# PiDGCv2.net
KiCad netlist of a schematic drawn in EAGLE
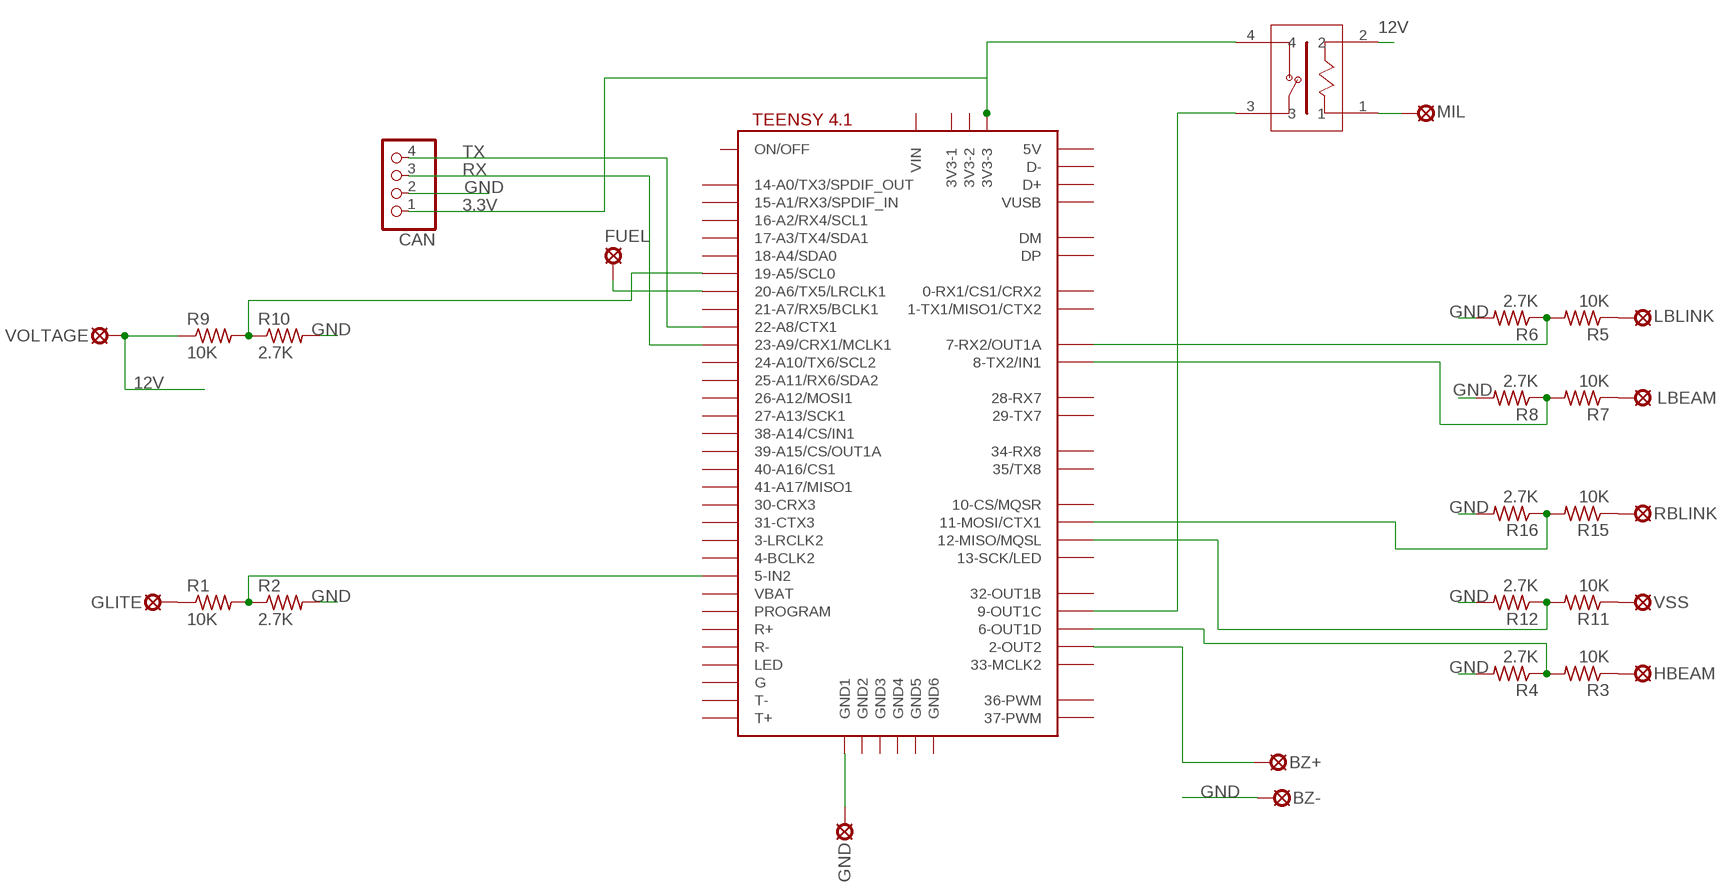
[diagram p0: schematic, sheet 1]

(export (version "E")
  (design (tool "Eeschema 10.0.6"))
  (components
    (comp (ref "BZ+")
      (value "LSP10")
      (footprint "eagle-import:LSP10")
      (libsource (lib "eagle-import") (part "LSP10"))
    )
    (comp (ref "BZ-")
      (value "LSP10")
      (footprint "eagle-import:LSP10")
      (libsource (lib "eagle-import") (part "LSP10"))
    )
    (comp (ref "CAN")
      (value "PINHD-1X4")
      (footprint "eagle-import:1X04")
      (libsource (lib "eagle-import") (part "PINHD-1X4"))
    )
    (comp (ref "FUEL")
      (value "LSP10")
      (footprint "eagle-import:LSP10")
      (libsource (lib "eagle-import") (part "LSP10"))
    )
    (comp (ref "GLITE")
      (value "LSP10")
      (footprint "eagle-import:LSP10")
      (libsource (lib "eagle-import") (part "LSP10"))
    )
    (comp (ref "GND")
      (value "LSP10")
      (footprint "eagle-import:LSP10")
      (libsource (lib "eagle-import") (part "LSP10"))
    )
    (comp (ref "HBEAM")
      (value "LSP10")
      (footprint "eagle-import:LSP10")
      (libsource (lib "eagle-import") (part "LSP10"))
    )
    (comp (ref "LBEAM")
      (value "LSP10")
      (footprint "eagle-import:LSP10")
      (libsource (lib "eagle-import") (part "LSP10"))
    )
    (comp (ref "LBLINK")
      (value "LSP10")
      (footprint "eagle-import:LSP10")
      (libsource (lib "eagle-import") (part "LSP10"))
    )
    (comp (ref "MIL")
      (value "LSP10")
      (footprint "eagle-import:LSP10")
      (libsource (lib "eagle-import") (part "LSP10"))
    )
    (comp (ref "MIL_RELAY")
      (value "BR-1050-VP")
      (footprint "eagle-import:RELAY")
      (libsource (lib "eagle-import") (part "BR-1050-VP"))
    )
    (comp (ref "R1")
      (value "10K")
      (footprint "eagle-import:0204_7")
      (libsource (lib "eagle-import") (part "R-US_0204/7"))
    )
    (comp (ref "R2")
      (value "2.7K")
      (footprint "eagle-import:0204_7")
      (libsource (lib "eagle-import") (part "R-US_0204/7"))
    )
    (comp (ref "R3")
      (value "10K")
      (footprint "eagle-import:0204_7")
      (libsource (lib "eagle-import") (part "R-US_0204/7"))
    )
    (comp (ref "R4")
      (value "2.7K")
      (footprint "eagle-import:0204_7")
      (libsource (lib "eagle-import") (part "R-US_0204/7"))
    )
    (comp (ref "R5")
      (value "10K")
      (footprint "eagle-import:0204_7")
      (libsource (lib "eagle-import") (part "R-US_0204/7"))
    )
    (comp (ref "R6")
      (value "2.7K")
      (footprint "eagle-import:0204_7")
      (libsource (lib "eagle-import") (part "R-US_0204/7"))
    )
    (comp (ref "R7")
      (value "10K")
      (footprint "eagle-import:0204_7")
      (libsource (lib "eagle-import") (part "R-US_0204/7"))
    )
    (comp (ref "R8")
      (value "2.7K")
      (footprint "eagle-import:0204_7")
      (libsource (lib "eagle-import") (part "R-US_0204/7"))
    )
    (comp (ref "R9")
      (value "10K")
      (footprint "eagle-import:0204_7")
      (libsource (lib "eagle-import") (part "R-US_0204/7"))
    )
    (comp (ref "R10")
      (value "2.7K")
      (footprint "eagle-import:0204_7")
      (libsource (lib "eagle-import") (part "R-US_0204/7"))
    )
    (comp (ref "R11")
      (value "10K")
      (footprint "eagle-import:0204_7")
      (libsource (lib "eagle-import") (part "R-US_0204/7"))
    )
    (comp (ref "R12")
      (value "2.7K")
      (footprint "eagle-import:0204_7")
      (libsource (lib "eagle-import") (part "R-US_0204/7"))
    )
    (comp (ref "R15")
      (value "10K")
      (footprint "eagle-import:0204_7")
      (libsource (lib "eagle-import") (part "R-US_0204/7"))
    )
    (comp (ref "R16")
      (value "2.7K")
      (footprint "eagle-import:0204_7")
      (libsource (lib "eagle-import") (part "R-US_0204/7"))
    )
    (comp (ref "RBLINK")
      (value "LSP10")
      (footprint "eagle-import:LSP10")
      (libsource (lib "eagle-import") (part "LSP10"))
    )
    (comp (ref "U$1")
      (value "TEENSY41")
      (footprint "eagle-import:TEENSY41")
      (libsource (lib "eagle-import") (part "TEENSY41"))
    )
    (comp (ref "VOLTAGE")
      (value "LSP10")
      (footprint "eagle-import:LSP10")
      (libsource (lib "eagle-import") (part "LSP10"))
    )
    (comp (ref "VSS")
      (value "LSP10")
      (footprint "eagle-import:LSP10")
      (libsource (lib "eagle-import") (part "LSP10"))
    )
  )
  (nets
    (net (code "1") (name "/3.3V") (class "Default")
      (node (ref "CAN") (pin "1") (pinfunction "1_1") (pintype "passive"))
      (node (ref "MIL_RELAY") (pin "4") (pinfunction "4_4") (pintype "bidirectional"))
      (node (ref "U$1") (pin "3V3-3") (pinfunction "3V3-3_3V3-3") (pintype "bidirectional"))
    )
    (net (code "2") (name "/12V") (class "Default")
      (node (ref "MIL_RELAY") (pin "2") (pinfunction "2_2") (pintype "bidirectional"))
      (node (ref "R9") (pin "1") (pinfunction "1_1") (pintype "passive"))
      (node (ref "VOLTAGE") (pin "MP") (pinfunction "MP_MP") (pintype "passive"))
    )
    (net (code "3") (name "/GND") (class "Default")
      (node (ref "BZ-") (pin "MP") (pinfunction "MP_MP") (pintype "passive"))
      (node (ref "CAN") (pin "2") (pinfunction "2_2") (pintype "passive"))
      (node (ref "GND") (pin "MP") (pinfunction "MP_MP") (pintype "passive"))
      (node (ref "R10") (pin "2") (pinfunction "2_2") (pintype "passive"))
      (node (ref "R12") (pin "2") (pinfunction "2_2") (pintype "passive"))
      (node (ref "R16") (pin "2") (pinfunction "2_2") (pintype "passive"))
      (node (ref "R2") (pin "2") (pinfunction "2_2") (pintype "passive"))
      (node (ref "R4") (pin "2") (pinfunction "2_2") (pintype "passive"))
      (node (ref "R6") (pin "2") (pinfunction "2_2") (pintype "passive"))
      (node (ref "R8") (pin "2") (pinfunction "2_2") (pintype "passive"))
      (node (ref "U$1") (pin "GND1") (pinfunction "GND1_GND1") (pintype "bidirectional"))
    )
    (net (code "4") (name "/RX") (class "Default")
      (node (ref "CAN") (pin "3") (pinfunction "3_3") (pintype "passive"))
      (node (ref "U$1") (pin "23-A9/CRX1/MCLK1") (pinfunction "23-A9/CRX1/MCLK1_23-A9/CRX1/MCLK1") (pintype "bidirectional"))
    )
    (net (code "5") (name "/TX") (class "Default")
      (node (ref "CAN") (pin "4") (pinfunction "4_4") (pintype "passive"))
      (node (ref "U$1") (pin "22-A8/CTX1") (pinfunction "22-A8/CTX1_22-A8/CTX1") (pintype "bidirectional"))
    )
    (net (code "6") (name "Net-(BZ+-PadMP)") (class "Default")
      (node (ref "BZ+") (pin "MP") (pinfunction "MP_MP") (pintype "passive"))
      (node (ref "U$1") (pin "2-OUT2") (pinfunction "2-OUT2_2-OUT2") (pintype "bidirectional"))
    )
    (net (code "7") (name "Net-(FUEL-PadMP)") (class "Default")
      (node (ref "FUEL") (pin "MP") (pinfunction "MP_MP") (pintype "passive"))
      (node (ref "U$1") (pin "20-A6/TX5/LRCLK1") (pinfunction "20-A6/TX5/LRCLK1_20-A6/TX5/LRCLK1") (pintype "bidirectional"))
    )
    (net (code "8") (name "Net-(GLITE-PadMP)") (class "Default")
      (node (ref "GLITE") (pin "MP") (pinfunction "MP_MP") (pintype "passive"))
      (node (ref "R1") (pin "1") (pinfunction "1_1") (pintype "passive"))
    )
    (net (code "9") (name "Net-(HBEAM-PadMP)") (class "Default")
      (node (ref "HBEAM") (pin "MP") (pinfunction "MP_MP") (pintype "passive"))
      (node (ref "R3") (pin "1") (pinfunction "1_1") (pintype "passive"))
    )
    (net (code "10") (name "Net-(LBEAM-PadMP)") (class "Default")
      (node (ref "LBEAM") (pin "MP") (pinfunction "MP_MP") (pintype "passive"))
      (node (ref "R7") (pin "1") (pinfunction "1_1") (pintype "passive"))
    )
    (net (code "11") (name "Net-(LBLINK-PadMP)") (class "Default")
      (node (ref "LBLINK") (pin "MP") (pinfunction "MP_MP") (pintype "passive"))
      (node (ref "R5") (pin "1") (pinfunction "1_1") (pintype "passive"))
    )
    (net (code "12") (name "Net-(MIL-PadMP)") (class "Default")
      (node (ref "MIL") (pin "MP") (pinfunction "MP_MP") (pintype "passive"))
      (node (ref "MIL_RELAY") (pin "1") (pinfunction "1_1") (pintype "bidirectional"))
    )
    (net (code "13") (name "Net-(MIL_RELAY-Pad3)") (class "Default")
      (node (ref "MIL_RELAY") (pin "3") (pinfunction "3_3") (pintype "bidirectional"))
      (node (ref "U$1") (pin "9-OUT1C") (pinfunction "9-OUT1C_9-OUT1C") (pintype "bidirectional"))
    )
    (net (code "14") (name "Net-(R1-Pad2)") (class "Default")
      (node (ref "R1") (pin "2") (pinfunction "2_2") (pintype "passive"))
      (node (ref "R2") (pin "1") (pinfunction "1_1") (pintype "passive"))
      (node (ref "U$1") (pin "5-IN2") (pinfunction "5-IN2_5-IN2") (pintype "bidirectional"))
    )
    (net (code "15") (name "Net-(R3-Pad2)") (class "Default")
      (node (ref "R3") (pin "2") (pinfunction "2_2") (pintype "passive"))
      (node (ref "R4") (pin "1") (pinfunction "1_1") (pintype "passive"))
      (node (ref "U$1") (pin "6-OUT1D") (pinfunction "6-OUT1D_6-OUT1D") (pintype "bidirectional"))
    )
    (net (code "16") (name "Net-(R5-Pad2)") (class "Default")
      (node (ref "R5") (pin "2") (pinfunction "2_2") (pintype "passive"))
      (node (ref "R6") (pin "1") (pinfunction "1_1") (pintype "passive"))
      (node (ref "U$1") (pin "7-RX2/OUT1A") (pinfunction "7-RX2/OUT1A_7-RX2/OUT1A") (pintype "bidirectional"))
    )
    (net (code "17") (name "Net-(R10-Pad1)") (class "Default")
      (node (ref "R10") (pin "1") (pinfunction "1_1") (pintype "passive"))
      (node (ref "R9") (pin "2") (pinfunction "2_2") (pintype "passive"))
      (node (ref "U$1") (pin "19-A5/SCL0") (pinfunction "19-A5/SCL0_19-A5/SCL0") (pintype "bidirectional"))
    )
    (net (code "18") (name "Net-(R11-Pad1)") (class "Default")
      (node (ref "R11") (pin "1") (pinfunction "1_1") (pintype "passive"))
      (node (ref "VSS") (pin "MP") (pinfunction "MP_MP") (pintype "passive"))
    )
    (net (code "19") (name "Net-(R11-Pad2)") (class "Default")
      (node (ref "R11") (pin "2") (pinfunction "2_2") (pintype "passive"))
      (node (ref "R12") (pin "1") (pinfunction "1_1") (pintype "passive"))
      (node (ref "U$1") (pin "12-MISO/MQSL") (pinfunction "12-MISO/MQSL_12-MISO/MQSL") (pintype "bidirectional"))
    )
    (net (code "20") (name "Net-(R15-Pad1)") (class "Default")
      (node (ref "R15") (pin "1") (pinfunction "1_1") (pintype "passive"))
      (node (ref "RBLINK") (pin "MP") (pinfunction "MP_MP") (pintype "passive"))
    )
    (net (code "21") (name "Net-(R15-Pad2)") (class "Default")
      (node (ref "R15") (pin "2") (pinfunction "2_2") (pintype "passive"))
      (node (ref "R16") (pin "1") (pinfunction "1_1") (pintype "passive"))
      (node (ref "U$1") (pin "11-MOSI/CTX1") (pinfunction "11-MOSI/CTX1_11-MOSI/CTX1") (pintype "bidirectional"))
    )
    (net (code "22") (name "Net-(U$1-8-TX2{slash}IN1)") (class "Default")
      (node (ref "R7") (pin "2") (pinfunction "2_2") (pintype "passive"))
      (node (ref "R8") (pin "1") (pinfunction "1_1") (pintype "passive"))
      (node (ref "U$1") (pin "8-TX2/IN2") (pinfunction "8-TX2/IN1_8-TX2/IN2") (pintype "bidirectional"))
    )
    (net (code "23") (name "unconnected-(U$1-5V-Pad+5V)") (class "Default")
      (node (ref "U$1") (pin "+5V") (pinfunction "5V_+5V") (pintype "bidirectional"))
    )
    (net (code "24") (name "unconnected-(U$1-10-CS{slash}MQSR-Pad10-CS\\MQSR)") (class "Default")
      (node (ref "U$1") (pin "10-CS\\MQSR") (pinfunction "10-CS/MQSR_10-CS\\MQSR") (pintype "bidirectional"))
    )
    (net (code "25") (name "unconnected-(U$1-35{slash}TX8-Pad35-TX8)") (class "Default")
      (node (ref "U$1") (pin "35-TX8") (pinfunction "35/TX8_35-TX8") (pintype "bidirectional"))
    )
    (net (code "26") (name "unconnected-(U$1-Pad0-RX1{slash}CS1{slash}CRX2)") (class "Default")
      (node (ref "U$1") (pin "0-RX1/CS1/CRX2") (pinfunction "0-RX1/CS1/CRX2_0-RX1/CS1/CRX2") (pintype "bidirectional"))
    )
    (net (code "27") (name "unconnected-(U$1-Pad1-TX1{slash}MISO1{slash}CTX2)") (class "Default")
      (node (ref "U$1") (pin "1-TX1/MISO1/CTX2") (pinfunction "1-TX1/MISO1/CTX2_1-TX1/MISO1/CTX2") (pintype "bidirectional"))
    )
    (net (code "28") (name "unconnected-(U$1-Pad3-LRCLK2)") (class "Default")
      (node (ref "U$1") (pin "3-LRCLK2") (pinfunction "3-LRCLK2_3-LRCLK2") (pintype "bidirectional"))
    )
    (net (code "29") (name "unconnected-(U$1-Pad3V3-1)") (class "Default")
      (node (ref "U$1") (pin "3V3-1") (pinfunction "3V3-1_3V3-1") (pintype "bidirectional"))
    )
    (net (code "30") (name "unconnected-(U$1-Pad3V3-2)") (class "Default")
      (node (ref "U$1") (pin "3V3-2") (pinfunction "3V3-2_3V3-2") (pintype "bidirectional"))
    )
    (net (code "31") (name "unconnected-(U$1-Pad4-BCLK2)") (class "Default")
      (node (ref "U$1") (pin "4-BCLK2") (pinfunction "4-BCLK2_4-BCLK2") (pintype "bidirectional"))
    )
    (net (code "32") (name "unconnected-(U$1-Pad13-SCK{slash}LED)") (class "Default")
      (node (ref "U$1") (pin "13-SCK/LED") (pinfunction "13-SCK/LED_13-SCK/LED") (pintype "bidirectional"))
    )
    (net (code "33") (name "unconnected-(U$1-Pad14-A0{slash}TX3{slash}SPDIF_OUT)") (class "Default")
      (node (ref "U$1") (pin "14-A0/TX3/SPDIF_OUT") (pinfunction "14-A0/TX3/SPDIF_OUT_14-A0/TX3/SPDIF_OUT") (pintype "bidirectional"))
    )
    (net (code "34") (name "unconnected-(U$1-Pad15-A1{slash}RX3{slash}SPDIF_IN)") (class "Default")
      (node (ref "U$1") (pin "15-A1/RX3/SPDIF_IN") (pinfunction "15-A1/RX3/SPDIF_IN_15-A1/RX3/SPDIF_IN") (pintype "bidirectional"))
    )
    (net (code "35") (name "unconnected-(U$1-Pad16-A2{slash}RX4{slash}SCL1)") (class "Default")
      (node (ref "U$1") (pin "16-A2/RX4/SCL1") (pinfunction "16-A2/RX4/SCL1_16-A2/RX4/SCL1") (pintype "bidirectional"))
    )
    (net (code "36") (name "unconnected-(U$1-Pad17-A3{slash}TX4{slash}SDA1)") (class "Default")
      (node (ref "U$1") (pin "17-A3/TX4/SDA1") (pinfunction "17-A3/TX4/SDA1_17-A3/TX4/SDA1") (pintype "bidirectional"))
    )
    (net (code "37") (name "unconnected-(U$1-Pad18-A4{slash}SDA0)") (class "Default")
      (node (ref "U$1") (pin "18-A4/SDA0") (pinfunction "18-A4/SDA0_18-A4/SDA0") (pintype "bidirectional"))
    )
    (net (code "38") (name "unconnected-(U$1-Pad21-A7{slash}RX5{slash}BCLK1)") (class "Default")
      (node (ref "U$1") (pin "21-A7/RX5/BCLK1") (pinfunction "21-A7/RX5/BCLK1_21-A7/RX5/BCLK1") (pintype "bidirectional"))
    )
    (net (code "39") (name "unconnected-(U$1-Pad24-A10{slash}TX6{slash}SCL2)") (class "Default")
      (node (ref "U$1") (pin "24-A10/TX6/SCL2") (pinfunction "24-A10/TX6/SCL2_24-A10/TX6/SCL2") (pintype "bidirectional"))
    )
    (net (code "40") (name "unconnected-(U$1-Pad25-A11{slash}RX6{slash}SDA2)") (class "Default")
      (node (ref "U$1") (pin "25-A11/RX6/SDA2") (pinfunction "25-A11/RX6/SDA2_25-A11/RX6/SDA2") (pintype "bidirectional"))
    )
    (net (code "41") (name "unconnected-(U$1-Pad26-A12{slash}MOSI1)") (class "Default")
      (node (ref "U$1") (pin "26-A12/MOSI1") (pinfunction "26-A12/MOSI1_26-A12/MOSI1") (pintype "bidirectional"))
    )
    (net (code "42") (name "unconnected-(U$1-Pad27-A13{slash}SCK1)") (class "Default")
      (node (ref "U$1") (pin "27-A13/SCK1") (pinfunction "27-A13/SCK1_27-A13/SCK1") (pintype "bidirectional"))
    )
    (net (code "43") (name "unconnected-(U$1-Pad28-RX7)") (class "Default")
      (node (ref "U$1") (pin "28-RX7") (pinfunction "28-RX7_28-RX7") (pintype "bidirectional"))
    )
    (net (code "44") (name "unconnected-(U$1-Pad29-TX7)") (class "Default")
      (node (ref "U$1") (pin "29-TX7") (pinfunction "29-TX7_29-TX7") (pintype "bidirectional"))
    )
    (net (code "45") (name "unconnected-(U$1-Pad30-CRX3)") (class "Default")
      (node (ref "U$1") (pin "30-CRX3") (pinfunction "30-CRX3_30-CRX3") (pintype "bidirectional"))
    )
    (net (code "46") (name "unconnected-(U$1-Pad31-CTX3)") (class "Default")
      (node (ref "U$1") (pin "31-CTX3") (pinfunction "31-CTX3_31-CTX3") (pintype "bidirectional"))
    )
    (net (code "47") (name "unconnected-(U$1-Pad32-OUT1B)") (class "Default")
      (node (ref "U$1") (pin "32-OUT1B") (pinfunction "32-OUT1B_32-OUT1B") (pintype "bidirectional"))
    )
    (net (code "48") (name "unconnected-(U$1-Pad33-MCLK2)") (class "Default")
      (node (ref "U$1") (pin "33-MCLK2") (pinfunction "33-MCLK2_33-MCLK2") (pintype "bidirectional"))
    )
    (net (code "49") (name "unconnected-(U$1-Pad34-RX8)") (class "Default")
      (node (ref "U$1") (pin "34-RX8") (pinfunction "34-RX8_34-RX8") (pintype "bidirectional"))
    )
    (net (code "50") (name "unconnected-(U$1-Pad36-PWM)") (class "Default")
      (node (ref "U$1") (pin "36-PWM") (pinfunction "36-PWM_36-PWM") (pintype "bidirectional"))
    )
    (net (code "51") (name "unconnected-(U$1-Pad37-PWM)") (class "Default")
      (node (ref "U$1") (pin "37-PWM") (pinfunction "37-PWM_37-PWM") (pintype "bidirectional"))
    )
    (net (code "52") (name "unconnected-(U$1-Pad38-A14{slash}CS{slash}IN1)") (class "Default")
      (node (ref "U$1") (pin "38-A14/CS/IN1") (pinfunction "38-A14/CS/IN1_38-A14/CS/IN1") (pintype "bidirectional"))
    )
    (net (code "53") (name "unconnected-(U$1-Pad39-A15{slash}CS{slash}OUT1A)") (class "Default")
      (node (ref "U$1") (pin "39-A15/CS/OUT1A") (pinfunction "39-A15/CS/OUT1A_39-A15/CS/OUT1A") (pintype "bidirectional"))
    )
    (net (code "54") (name "unconnected-(U$1-Pad40-A16{slash}CS1)") (class "Default")
      (node (ref "U$1") (pin "40-A16/CS1") (pinfunction "40-A16/CS1_40-A16/CS1") (pintype "bidirectional"))
    )
    (net (code "55") (name "unconnected-(U$1-Pad41-A17{slash}MISO1)") (class "Default")
      (node (ref "U$1") (pin "41-A17/MISO1") (pinfunction "41-A17/MISO1_41-A17/MISO1") (pintype "bidirectional"))
    )
    (net (code "56") (name "unconnected-(U$1-PadD+)") (class "Default")
      (node (ref "U$1") (pin "D+") (pinfunction "D+_D+") (pintype "bidirectional"))
    )
    (net (code "57") (name "unconnected-(U$1-PadD-)") (class "Default")
      (node (ref "U$1") (pin "D-") (pinfunction "D-_D-") (pintype "bidirectional"))
    )
    (net (code "58") (name "unconnected-(U$1-PadDM)") (class "Default")
      (node (ref "U$1") (pin "DM") (pinfunction "DM_DM") (pintype "bidirectional"))
    )
    (net (code "59") (name "unconnected-(U$1-PadDP)") (class "Default")
      (node (ref "U$1") (pin "DP") (pinfunction "DP_DP") (pintype "bidirectional"))
    )
    (net (code "60") (name "unconnected-(U$1-PadG)") (class "Default")
      (node (ref "U$1") (pin "G") (pinfunction "G_G") (pintype "bidirectional"))
    )
    (net (code "61") (name "unconnected-(U$1-PadGND2)") (class "Default")
      (node (ref "U$1") (pin "GND2") (pinfunction "GND2_GND2") (pintype "bidirectional"))
    )
    (net (code "62") (name "unconnected-(U$1-PadGND3)") (class "Default")
      (node (ref "U$1") (pin "GND3") (pinfunction "GND3_GND3") (pintype "bidirectional"))
    )
    (net (code "63") (name "unconnected-(U$1-PadGND4)") (class "Default")
      (node (ref "U$1") (pin "GND4") (pinfunction "GND4_GND4") (pintype "bidirectional"))
    )
    (net (code "64") (name "unconnected-(U$1-PadGND5)") (class "Default")
      (node (ref "U$1") (pin "GND5") (pinfunction "GND5_GND5") (pintype "bidirectional"))
    )
    (net (code "65") (name "unconnected-(U$1-PadGND6)") (class "Default")
      (node (ref "U$1") (pin "GND6") (pinfunction "GND6_GND6") (pintype "bidirectional"))
    )
    (net (code "66") (name "unconnected-(U$1-PadLED)") (class "Default")
      (node (ref "U$1") (pin "LED") (pinfunction "LED_LED") (pintype "bidirectional"))
    )
    (net (code "67") (name "unconnected-(U$1-PadON{slash}OFF)") (class "Default")
      (node (ref "U$1") (pin "ON/OFF") (pinfunction "ON/OFF_ON/OFF") (pintype "bidirectional"))
    )
    (net (code "68") (name "unconnected-(U$1-PadPROGRAM)") (class "Default")
      (node (ref "U$1") (pin "PROGRAM") (pinfunction "PROGRAM_PROGRAM") (pintype "bidirectional"))
    )
    (net (code "69") (name "unconnected-(U$1-PadR+)") (class "Default")
      (node (ref "U$1") (pin "R+") (pinfunction "R+_R+") (pintype "bidirectional"))
    )
    (net (code "70") (name "unconnected-(U$1-PadR-)") (class "Default")
      (node (ref "U$1") (pin "R-") (pinfunction "R-_R-") (pintype "bidirectional"))
    )
    (net (code "71") (name "unconnected-(U$1-PadT+)") (class "Default")
      (node (ref "U$1") (pin "T+") (pinfunction "T+_T+") (pintype "bidirectional"))
    )
    (net (code "72") (name "unconnected-(U$1-PadT-)") (class "Default")
      (node (ref "U$1") (pin "T-") (pinfunction "T-_T-") (pintype "bidirectional"))
    )
    (net (code "73") (name "unconnected-(U$1-PadVBAT)") (class "Default")
      (node (ref "U$1") (pin "VBAT") (pinfunction "VBAT_VBAT") (pintype "bidirectional"))
    )
    (net (code "74") (name "unconnected-(U$1-PadVIN)") (class "Default")
      (node (ref "U$1") (pin "VIN") (pinfunction "VIN_VIN") (pintype "bidirectional"))
    )
    (net (code "75") (name "unconnected-(U$1-PadVUSB)") (class "Default")
      (node (ref "U$1") (pin "VUSB") (pinfunction "VUSB_VUSB") (pintype "bidirectional"))
    )
  )
)
